# Power_Board_V2.net
KiCad netlist of a schematic drawn in EAGLE
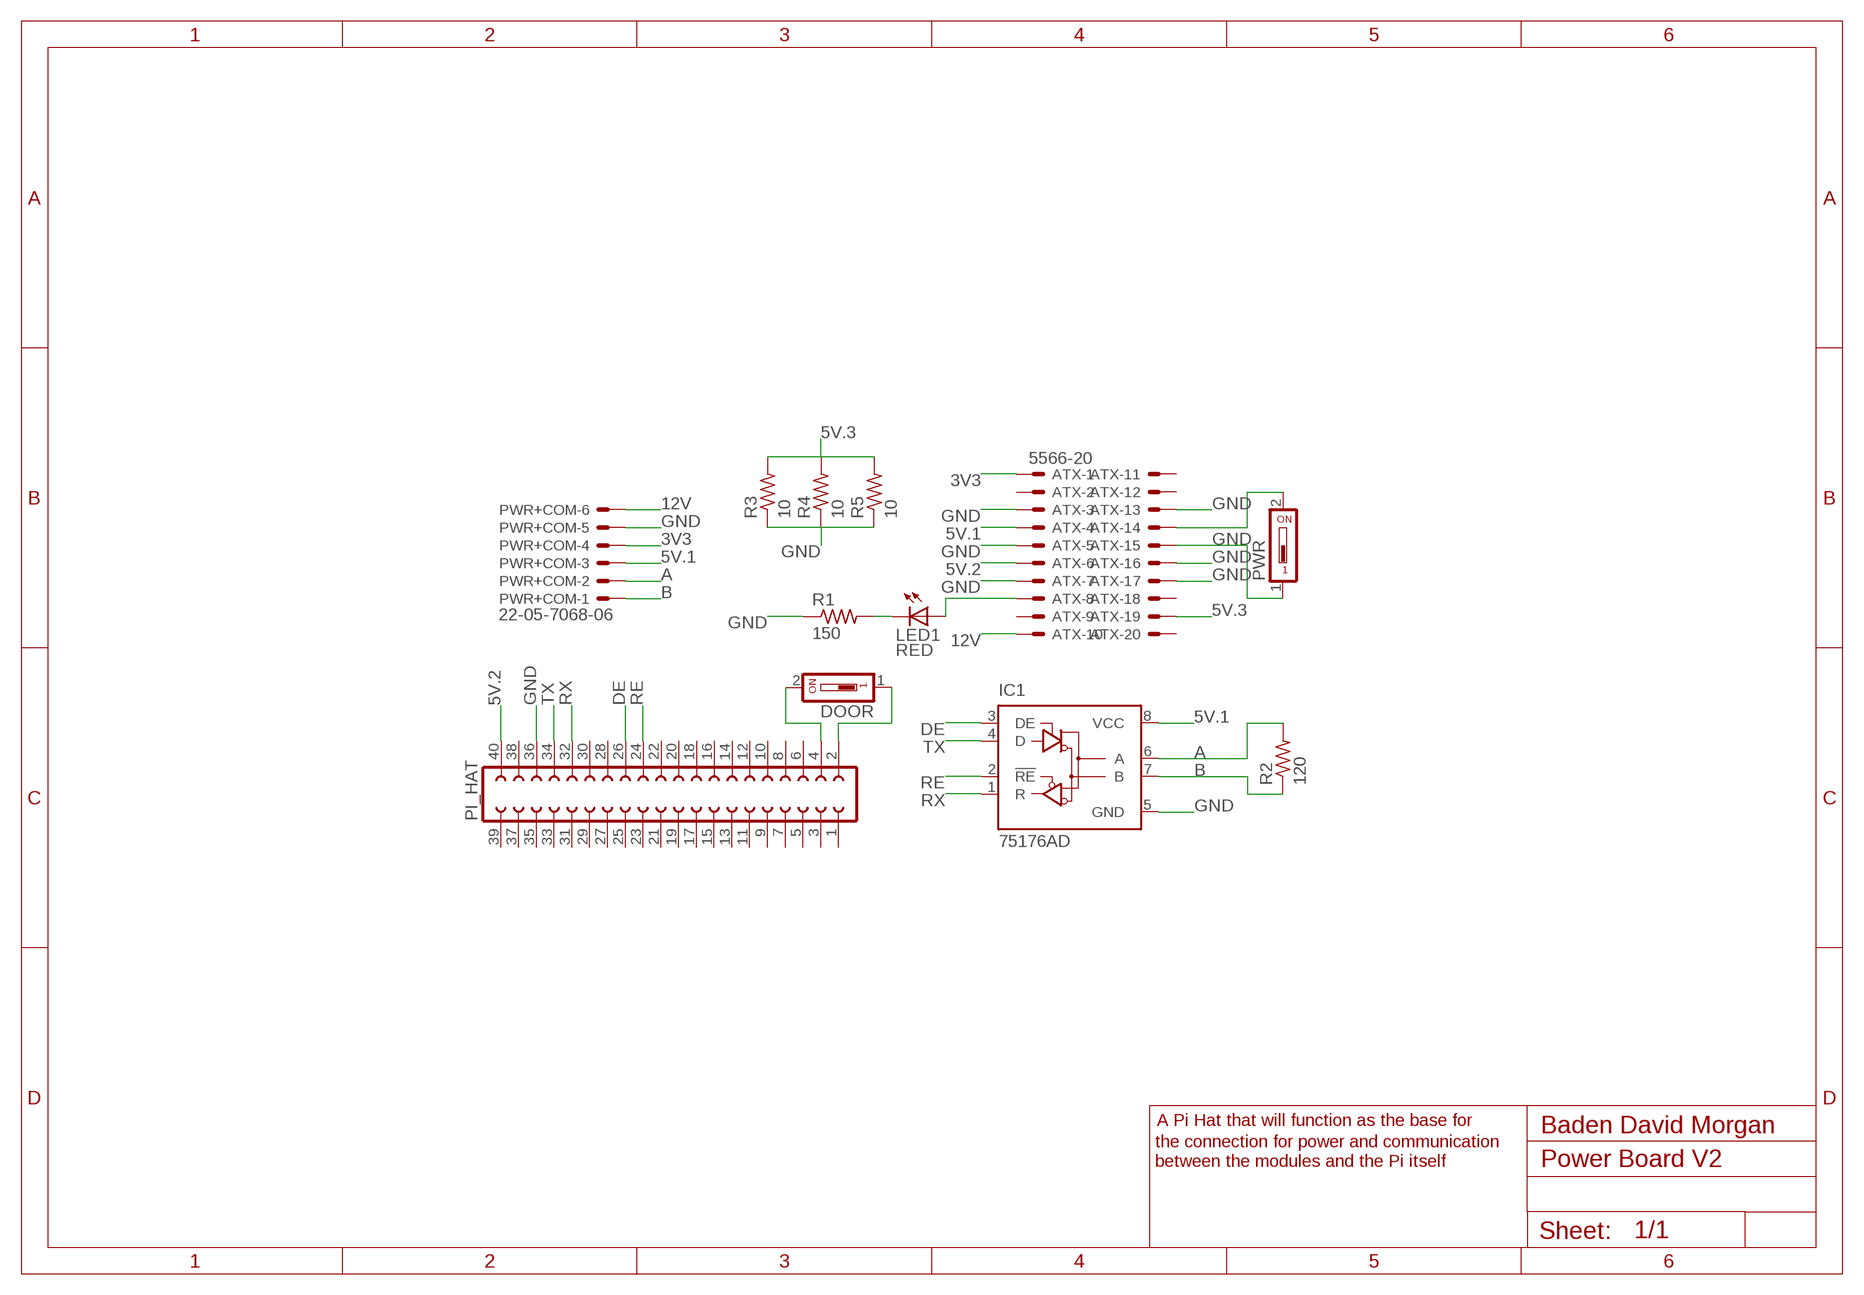
[diagram p0: schematic, sheet 1]

(export (version "E")
  (design (tool "Eeschema 10.0.6"))
  (components
    (comp (ref "ATX")
      (value "5566-20")
      (footprint "eagle-import:5566-20")
      (libsource (lib "eagle-import") (part "5566-20"))
    )
    (comp (ref "DOOR")
      (value "SD4-01")
      (footprint "eagle-import:SD4-01")
      (libsource (lib "eagle-import") (part "SD4-01"))
    )
    (comp (ref "IC1")
      (value "75176AD")
      (footprint "eagle-import:D_R-PDSO-G8")
      (libsource (lib "eagle-import") (part "75176AD"))
    )
    (comp (ref "LED1")
      (value "RED")
      (footprint "eagle-import:CHIPLED_1206")
      (libsource (lib "eagle-import") (part "LEDCHIPLED_1206"))
    )
    (comp (ref "PI_HAT")
      (value "FE20-2")
      (footprint "eagle-import:FE20-2")
      (libsource (lib "eagle-import") (part "FE20-2"))
    )
    (comp (ref "PWR")
      (value "SD4-01")
      (footprint "eagle-import:SD4-01")
      (libsource (lib "eagle-import") (part "SD4-01"))
    )
    (comp (ref "PWR+COM")
      (value "22-05-7068-06")
      (footprint "eagle-import:7395-06")
      (libsource (lib "eagle-import") (part "22-?-0605-7068"))
    )
    (comp (ref "R1")
      (value "150")
      (footprint "eagle-import:R0805")
      (libsource (lib "eagle-import") (part "resistor_R-US_R0805"))
    )
    (comp (ref "R2")
      (value "120")
      (footprint "eagle-import:R0805")
      (libsource (lib "eagle-import") (part "resistor_R-US_R0805"))
    )
    (comp (ref "R3")
      (value "10")
      (footprint "eagle-import:P0817V")
      (libsource (lib "eagle-import") (part "R-US_0817/7V"))
    )
    (comp (ref "R4")
      (value "10")
      (footprint "eagle-import:P0817V")
      (libsource (lib "eagle-import") (part "R-US_0817/7V"))
    )
    (comp (ref "R5")
      (value "10")
      (footprint "eagle-import:P0817V")
      (libsource (lib "eagle-import") (part "R-US_0817/7V"))
    )
  )
  (nets
    (net (code "1") (name "/3V3") (class "Default")
      (node (ref "ATX") (pin "1") (pinfunction "S_1") (pintype "passive"))
      (node (ref "PWR+COM") (pin "4") (pinfunction "S_4") (pintype "passive"))
    )
    (net (code "2") (name "/5V.1") (class "Default")
      (node (ref "ATX") (pin "4") (pinfunction "S_4") (pintype "passive"))
      (node (ref "IC1") (pin "8") (pinfunction "VCC_8") (pintype "power_in"))
      (node (ref "PWR+COM") (pin "3") (pinfunction "S_3") (pintype "passive"))
    )
    (net (code "3") (name "/5V.2") (class "Default")
      (node (ref "ATX") (pin "6") (pinfunction "S_6") (pintype "passive"))
      (node (ref "PI_HAT") (pin "40") (pinfunction "40_40") (pintype "passive"))
    )
    (net (code "4") (name "/5V.3") (class "Default")
      (node (ref "ATX") (pin "19") (pinfunction "S_19") (pintype "passive"))
      (node (ref "R3") (pin "2") (pinfunction "2_2") (pintype "passive"))
      (node (ref "R4") (pin "2") (pinfunction "2_2") (pintype "passive"))
      (node (ref "R5") (pin "2") (pinfunction "2_2") (pintype "passive"))
    )
    (net (code "5") (name "/12V") (class "Default")
      (node (ref "ATX") (pin "10") (pinfunction "S_10") (pintype "passive"))
      (node (ref "PWR+COM") (pin "6") (pinfunction "S_6") (pintype "passive"))
    )
    (net (code "6") (name "/A") (class "Default")
      (node (ref "IC1") (pin "6") (pinfunction "A_6") (pintype "output"))
      (node (ref "PWR+COM") (pin "2") (pinfunction "S_2") (pintype "passive"))
      (node (ref "R2") (pin "2") (pinfunction "2_2") (pintype "passive"))
    )
    (net (code "7") (name "/B") (class "Default")
      (node (ref "IC1") (pin "7") (pinfunction "B_7") (pintype "output"))
      (node (ref "PWR+COM") (pin "1") (pinfunction "S_1") (pintype "passive"))
      (node (ref "R2") (pin "1") (pinfunction "1_1") (pintype "passive"))
    )
    (net (code "8") (name "/DE") (class "Default")
      (node (ref "IC1") (pin "3") (pinfunction "DE_3") (pintype "input"))
      (node (ref "PI_HAT") (pin "26") (pinfunction "26_26") (pintype "passive"))
    )
    (net (code "9") (name "/GND") (class "Default")
      (node (ref "ATX") (pin "13") (pinfunction "S_13") (pintype "passive"))
      (node (ref "ATX") (pin "15") (pinfunction "S_15") (pintype "passive"))
      (node (ref "ATX") (pin "16") (pinfunction "S_16") (pintype "passive"))
      (node (ref "ATX") (pin "17") (pinfunction "S_17") (pintype "passive"))
      (node (ref "ATX") (pin "3") (pinfunction "S_3") (pintype "passive"))
      (node (ref "ATX") (pin "5") (pinfunction "S_5") (pintype "passive"))
      (node (ref "ATX") (pin "7") (pinfunction "S_7") (pintype "passive"))
      (node (ref "IC1") (pin "5") (pinfunction "GND_5") (pintype "power_in"))
      (node (ref "PI_HAT") (pin "36") (pinfunction "36_36") (pintype "passive"))
      (node (ref "PWR") (pin "1") (pinfunction "1_1") (pintype "passive"))
      (node (ref "PWR+COM") (pin "5") (pinfunction "S_5") (pintype "passive"))
      (node (ref "R1") (pin "1") (pinfunction "1_1") (pintype "passive"))
      (node (ref "R3") (pin "1") (pinfunction "1_1") (pintype "passive"))
      (node (ref "R4") (pin "1") (pinfunction "1_1") (pintype "passive"))
      (node (ref "R5") (pin "1") (pinfunction "1_1") (pintype "passive"))
    )
    (net (code "10") (name "/RE") (class "Default")
      (node (ref "IC1") (pin "2") (pinfunction "~{RE}_2") (pintype "input"))
      (node (ref "PI_HAT") (pin "24") (pinfunction "24_24") (pintype "passive"))
    )
    (net (code "11") (name "/RX") (class "Default")
      (node (ref "IC1") (pin "1") (pinfunction "R_1") (pintype "input"))
      (node (ref "PI_HAT") (pin "32") (pinfunction "32_32") (pintype "passive"))
    )
    (net (code "12") (name "/TX") (class "Default")
      (node (ref "IC1") (pin "4") (pinfunction "D_4") (pintype "input"))
      (node (ref "PI_HAT") (pin "34") (pinfunction "34_34") (pintype "passive"))
    )
    (net (code "13") (name "Net-(ATXF-S)") (class "Default")
      (node (ref "ATX") (pin "14") (pinfunction "S_14") (pintype "passive"))
      (node (ref "PWR") (pin "2") (pinfunction "2_2") (pintype "passive"))
    )
    (net (code "14") (name "Net-(ATXS-S)") (class "Default")
      (node (ref "ATX") (pin "8") (pinfunction "S_8") (pintype "passive"))
      (node (ref "LED1") (pin "A") (pinfunction "A_A") (pintype "passive"))
    )
    (net (code "15") (name "Net-(DOOR-Pad1)") (class "Default")
      (node (ref "DOOR") (pin "1") (pinfunction "1_1") (pintype "passive"))
      (node (ref "PI_HAT") (pin "2") (pinfunction "2_2") (pintype "passive"))
    )
    (net (code "16") (name "Net-(DOOR-Pad2)") (class "Default")
      (node (ref "DOOR") (pin "2") (pinfunction "2_2") (pintype "passive"))
      (node (ref "PI_HAT") (pin "4") (pinfunction "4_4") (pintype "passive"))
    )
    (net (code "17") (name "Net-(LED1-PadC)") (class "Default")
      (node (ref "LED1") (pin "C") (pinfunction "C_C") (pintype "passive"))
      (node (ref "R1") (pin "2") (pinfunction "2_2") (pintype "passive"))
    )
    (net (code "18") (name "unconnected-(ATXC-S-Pad11)") (class "Default")
      (node (ref "ATX") (pin "11") (pinfunction "S_11") (pintype "passive"))
    )
    (net (code "19") (name "unconnected-(ATXD-S-Pad12)") (class "Default")
      (node (ref "ATX") (pin "12") (pinfunction "S_12") (pintype "passive"))
    )
    (net (code "20") (name "unconnected-(ATXJ-S-Pad18)") (class "Default")
      (node (ref "ATX") (pin "18") (pinfunction "S_18") (pintype "passive"))
    )
    (net (code "21") (name "unconnected-(ATXL-S-Pad2)") (class "Default")
      (node (ref "ATX") (pin "2") (pinfunction "S_2") (pintype "passive"))
    )
    (net (code "22") (name "unconnected-(ATXM-S-Pad20)") (class "Default")
      (node (ref "ATX") (pin "20") (pinfunction "S_20") (pintype "passive"))
    )
    (net (code "23") (name "unconnected-(ATXT-S-Pad9)") (class "Default")
      (node (ref "ATX") (pin "9") (pinfunction "S_9") (pintype "passive"))
    )
    (net (code "24") (name "unconnected-(PI_HAT-Pad1)") (class "Default")
      (node (ref "PI_HAT") (pin "1") (pinfunction "1_1") (pintype "passive"))
    )
    (net (code "25") (name "unconnected-(PI_HAT-Pad3)") (class "Default")
      (node (ref "PI_HAT") (pin "3") (pinfunction "3_3") (pintype "passive"))
    )
    (net (code "26") (name "unconnected-(PI_HAT-Pad5)") (class "Default")
      (node (ref "PI_HAT") (pin "5") (pinfunction "5_5") (pintype "passive"))
    )
    (net (code "27") (name "unconnected-(PI_HAT-Pad6)") (class "Default")
      (node (ref "PI_HAT") (pin "6") (pinfunction "6_6") (pintype "passive"))
    )
    (net (code "28") (name "unconnected-(PI_HAT-Pad7)") (class "Default")
      (node (ref "PI_HAT") (pin "7") (pinfunction "7_7") (pintype "passive"))
    )
    (net (code "29") (name "unconnected-(PI_HAT-Pad8)") (class "Default")
      (node (ref "PI_HAT") (pin "8") (pinfunction "8_8") (pintype "passive"))
    )
    (net (code "30") (name "unconnected-(PI_HAT-Pad9)") (class "Default")
      (node (ref "PI_HAT") (pin "9") (pinfunction "9_9") (pintype "passive"))
    )
    (net (code "31") (name "unconnected-(PI_HAT-Pad10)") (class "Default")
      (node (ref "PI_HAT") (pin "10") (pinfunction "10_10") (pintype "passive"))
    )
    (net (code "32") (name "unconnected-(PI_HAT-Pad11)") (class "Default")
      (node (ref "PI_HAT") (pin "11") (pinfunction "11_11") (pintype "passive"))
    )
    (net (code "33") (name "unconnected-(PI_HAT-Pad12)") (class "Default")
      (node (ref "PI_HAT") (pin "12") (pinfunction "12_12") (pintype "passive"))
    )
    (net (code "34") (name "unconnected-(PI_HAT-Pad13)") (class "Default")
      (node (ref "PI_HAT") (pin "13") (pinfunction "13_13") (pintype "passive"))
    )
    (net (code "35") (name "unconnected-(PI_HAT-Pad14)") (class "Default")
      (node (ref "PI_HAT") (pin "14") (pinfunction "14_14") (pintype "passive"))
    )
    (net (code "36") (name "unconnected-(PI_HAT-Pad15)") (class "Default")
      (node (ref "PI_HAT") (pin "15") (pinfunction "15_15") (pintype "passive"))
    )
    (net (code "37") (name "unconnected-(PI_HAT-Pad16)") (class "Default")
      (node (ref "PI_HAT") (pin "16") (pinfunction "16_16") (pintype "passive"))
    )
    (net (code "38") (name "unconnected-(PI_HAT-Pad17)") (class "Default")
      (node (ref "PI_HAT") (pin "17") (pinfunction "17_17") (pintype "passive"))
    )
    (net (code "39") (name "unconnected-(PI_HAT-Pad18)") (class "Default")
      (node (ref "PI_HAT") (pin "18") (pinfunction "18_18") (pintype "passive"))
    )
    (net (code "40") (name "unconnected-(PI_HAT-Pad19)") (class "Default")
      (node (ref "PI_HAT") (pin "19") (pinfunction "19_19") (pintype "passive"))
    )
    (net (code "41") (name "unconnected-(PI_HAT-Pad20)") (class "Default")
      (node (ref "PI_HAT") (pin "20") (pinfunction "20_20") (pintype "passive"))
    )
    (net (code "42") (name "unconnected-(PI_HAT-Pad21)") (class "Default")
      (node (ref "PI_HAT") (pin "21") (pinfunction "21_21") (pintype "passive"))
    )
    (net (code "43") (name "unconnected-(PI_HAT-Pad22)") (class "Default")
      (node (ref "PI_HAT") (pin "22") (pinfunction "22_22") (pintype "passive"))
    )
    (net (code "44") (name "unconnected-(PI_HAT-Pad23)") (class "Default")
      (node (ref "PI_HAT") (pin "23") (pinfunction "23_23") (pintype "passive"))
    )
    (net (code "45") (name "unconnected-(PI_HAT-Pad25)") (class "Default")
      (node (ref "PI_HAT") (pin "25") (pinfunction "25_25") (pintype "passive"))
    )
    (net (code "46") (name "unconnected-(PI_HAT-Pad27)") (class "Default")
      (node (ref "PI_HAT") (pin "27") (pinfunction "27_27") (pintype "passive"))
    )
    (net (code "47") (name "unconnected-(PI_HAT-Pad28)") (class "Default")
      (node (ref "PI_HAT") (pin "28") (pinfunction "28_28") (pintype "passive"))
    )
    (net (code "48") (name "unconnected-(PI_HAT-Pad29)") (class "Default")
      (node (ref "PI_HAT") (pin "29") (pinfunction "29_29") (pintype "passive"))
    )
    (net (code "49") (name "unconnected-(PI_HAT-Pad30)") (class "Default")
      (node (ref "PI_HAT") (pin "30") (pinfunction "30_30") (pintype "passive"))
    )
    (net (code "50") (name "unconnected-(PI_HAT-Pad31)") (class "Default")
      (node (ref "PI_HAT") (pin "31") (pinfunction "31_31") (pintype "passive"))
    )
    (net (code "51") (name "unconnected-(PI_HAT-Pad33)") (class "Default")
      (node (ref "PI_HAT") (pin "33") (pinfunction "33_33") (pintype "passive"))
    )
    (net (code "52") (name "unconnected-(PI_HAT-Pad35)") (class "Default")
      (node (ref "PI_HAT") (pin "35") (pinfunction "35_35") (pintype "passive"))
    )
    (net (code "53") (name "unconnected-(PI_HAT-Pad37)") (class "Default")
      (node (ref "PI_HAT") (pin "37") (pinfunction "37_37") (pintype "passive"))
    )
    (net (code "54") (name "unconnected-(PI_HAT-Pad38)") (class "Default")
      (node (ref "PI_HAT") (pin "38") (pinfunction "38_38") (pintype "passive"))
    )
    (net (code "55") (name "unconnected-(PI_HAT-Pad39)") (class "Default")
      (node (ref "PI_HAT") (pin "39") (pinfunction "39_39") (pintype "passive"))
    )
  )
)
